# Main.net
KiCad netlist of a schematic drawn in Altium Designer
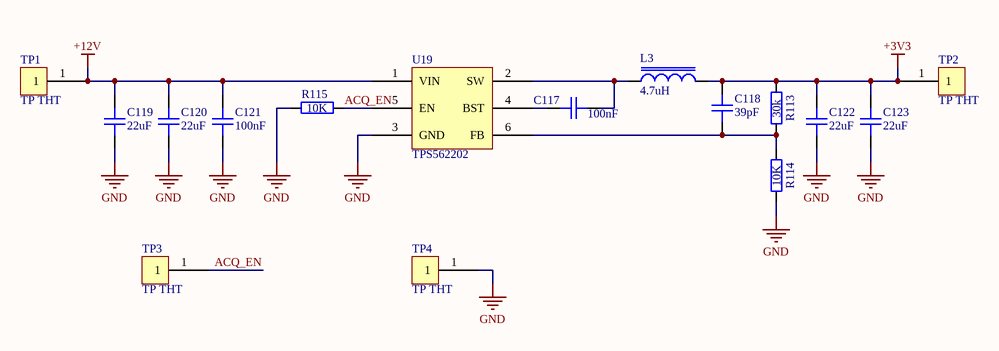
[diagram p0: Main.SchDoc]

(export (version "E")
  (design (tool "Eeschema 10.0.6"))
  (components
    (comp (ref "C117")
      (value "100nF")
      (footprint "GEN_C_0402")
      (fields
        (field (name "HOUSE PART NUMBER") "C-100nF-0402-002")
        (field (name "MANUFACTURER") "Murata")
        (field (name "MANUFACTURER PART NUMBER") "GCM155R71C104KA55D")
      )
      (libsource (lib "DSO") (part "CAP 100nF 16V X7R 0402"))
    )
    (comp (ref "C118")
      (value "39pF")
      (footprint "GEN_C_0402")
      (fields
        (field (name "MANUFACTURER") "KEMET")
        (field (name "HOUSE PART NUMBER") "C-39pF-0402-002")
        (field (name "MANUFACTURER PART NUMBER") "C0402C390J5GACTU")
      )
      (libsource (lib "DSO") (part "CAP 39pF 50V C0G 0402"))
    )
    (comp (ref "C119")
      (value "22uF")
      (footprint "GEN_C_0805")
      (fields
        (field (name "HOUSE PART NUMBER") "C-22uF-0805-002")
        (field (name "MANUFACTURER") "Murata")
        (field (name "MANUFACTURER PART NUMBER") "GRM21BR61E226ME44L")
      )
      (libsource (lib "DSO") (part "CAP 22uF 25V X5R 0805"))
    )
    (comp (ref "C120")
      (value "22uF")
      (footprint "GEN_C_0805")
      (fields
        (field (name "HOUSE PART NUMBER") "C-22uF-0805-002")
        (field (name "MANUFACTURER") "Murata")
        (field (name "MANUFACTURER PART NUMBER") "GRM21BR61E226ME44L")
      )
      (libsource (lib "DSO") (part "CAP 22uF 25V X5R 0805"))
    )
    (comp (ref "C121")
      (value "100nF")
      (footprint "GEN_C_0402")
      (fields
        (field (name "HOUSE PART NUMBER") "C-100nF-0402-002")
        (field (name "MANUFACTURER") "Murata")
        (field (name "MANUFACTURER PART NUMBER") "GCM155R71C104KA55D")
      )
      (libsource (lib "DSO") (part "CAP 100nF 16V X7R 0402"))
    )
    (comp (ref "C122")
      (value "22uF")
      (footprint "GEN_C_0805")
      (fields
        (field (name "HOUSE PART NUMBER") "C-22uF-0805-002")
        (field (name "MANUFACTURER") "Murata")
        (field (name "MANUFACTURER PART NUMBER") "GRM21BR61E226ME44L")
      )
      (libsource (lib "DSO") (part "CAP 22uF 25V X5R 0805"))
    )
    (comp (ref "C123")
      (value "22uF")
      (footprint "GEN_C_0805")
      (fields
        (field (name "HOUSE PART NUMBER") "C-22uF-0805-002")
        (field (name "MANUFACTURER") "Murata")
        (field (name "MANUFACTURER PART NUMBER") "GRM21BR61E226ME44L")
      )
      (libsource (lib "DSO") (part "CAP 22uF 25V X5R 0805"))
    )
    (comp (ref "L3")
      (value "4.7uH")
      (footprint "TY_IND_NRS5030")
      (fields
        (field (name "MANUFACTURER") "Taiyo Yuden")
        (field (name "MANUFACTURER PART NUMBER") "NRS5030T4R7MMGJ")
      )
      (libsource (lib "DSO") (part "IND 4.7uH 2.6A 35 MOHM SMD"))
    )
    (comp (ref "R113")
      (value "30k")
      (footprint "GEN_R_0402")
      (fields
        (field (name "TOLERANCE") "1%")
        (field (name "MANUFACTURER") "Yageo")
        (field (name "MANUFACTURER PART NUMBER") "RC0402FR-0730KL")
      )
      (libsource (lib "DSO") (part "RES 30K OHM 1% 1/16W 0402"))
    )
    (comp (ref "R114")
      (value "10K")
      (footprint "GEN_R_0402")
      (fields
        (field (name "TOLERANCE") "1%")
        (field (name "MANUFACTURER") "Panasonic")
        (field (name "MANUFACTURER PART NUMBER") "ERJ-2RKF1002X")
      )
      (libsource (lib "DSO") (part "RES 10K OHM 1% 1/10W 0402"))
    )
    (comp (ref "R115")
      (value "10K")
      (footprint "GEN_R_0402")
      (fields
        (field (name "TOLERANCE") "1%")
        (field (name "MANUFACTURER") "Panasonic")
        (field (name "MANUFACTURER PART NUMBER") "ERJ-2RKF1002X")
      )
      (libsource (lib "") (part "RES 10K OHM 1% 1/10W 0402_1"))
    )
    (comp (ref "TP1") (value "TP THT") (footprint "GEN_1_Pin_TH_TP") (libsource (lib "DSO") (part "TP THT")))
    (comp (ref "TP2") (value "TP THT") (footprint "GEN_1_Pin_TH_TP") (libsource (lib "") (part "TP THT_1")))
    (comp (ref "TP3") (value "TP THT") (footprint "GEN_1_Pin_TH_TP") (libsource (lib "DSO") (part "TP THT")))
    (comp (ref "TP4") (value "TP THT") (footprint "GEN_1_Pin_TH_TP") (libsource (lib "DSO") (part "TP THT")))
    (comp (ref "U19")
      (value "TPS562202")
      (footprint "TI_SOT563_DRL0006A")
      (libsource (lib "DSO") (part "IC BUCK TPS562202"))
    )
  )
  (nets
    (net (code "1") (name "+3V3") (class "Default")
      (node (ref "C118") (pin "2") (pinfunction "2_2") (pintype "passive"))
      (node (ref "C122") (pin "2") (pinfunction "2_2") (pintype "passive"))
      (node (ref "C123") (pin "2") (pinfunction "2_2") (pintype "passive"))
      (node (ref "L3") (pin "2") (pinfunction "2_2") (pintype "passive"))
      (node (ref "R113") (pin "2") (pinfunction "2_2") (pintype "passive"))
      (node (ref "TP2") (pin "1") (pinfunction "1_1") (pintype "passive"))
    )
    (net (code "2") (name "+12V") (class "Default")
      (node (ref "C119") (pin "2") (pinfunction "2_2") (pintype "passive"))
      (node (ref "C120") (pin "2") (pinfunction "2_2") (pintype "passive"))
      (node (ref "C121") (pin "1") (pinfunction "1_1") (pintype "passive"))
      (node (ref "TP1") (pin "1") (pinfunction "1_1") (pintype "passive"))
      (node (ref "U19") (pin "1") (pinfunction "VIN_1") (pintype "power_in"))
    )
    (net (code "3") (name "/ACQ_EN") (class "Default")
      (node (ref "R115") (pin "1") (pinfunction "1_1") (pintype "passive"))
      (node (ref "TP3") (pin "1") (pinfunction "1_1") (pintype "passive"))
      (node (ref "U19") (pin "5") (pinfunction "EN_5") (pintype "passive"))
    )
    (net (code "4") (name "GND") (class "Default")
      (node (ref "C119") (pin "1") (pinfunction "1_1") (pintype "passive"))
      (node (ref "C120") (pin "1") (pinfunction "1_1") (pintype "passive"))
      (node (ref "C121") (pin "2") (pinfunction "2_2") (pintype "passive"))
      (node (ref "C122") (pin "1") (pinfunction "1_1") (pintype "passive"))
      (node (ref "C123") (pin "1") (pinfunction "1_1") (pintype "passive"))
      (node (ref "R114") (pin "1") (pinfunction "1_1") (pintype "passive"))
      (node (ref "R115") (pin "2") (pinfunction "2_2") (pintype "passive"))
      (node (ref "TP4") (pin "1") (pinfunction "1_1") (pintype "passive"))
      (node (ref "U19") (pin "3") (pinfunction "GND_3") (pintype "power_in"))
    )
    (net (code "5") (name "Net-(U19-BST)") (class "Default")
      (node (ref "C117") (pin "2") (pinfunction "2_2") (pintype "passive"))
      (node (ref "U19") (pin "4") (pinfunction "BST_4") (pintype "passive"))
    )
    (net (code "6") (name "Net-(U19-FB)") (class "Default")
      (node (ref "C118") (pin "1") (pinfunction "1_1") (pintype "passive"))
      (node (ref "R113") (pin "1") (pinfunction "1_1") (pintype "passive"))
      (node (ref "R114") (pin "2") (pinfunction "2_2") (pintype "passive"))
      (node (ref "U19") (pin "6") (pinfunction "FB_6") (pintype "passive"))
    )
    (net (code "7") (name "Net-(U19-SW)") (class "Default")
      (node (ref "C117") (pin "1") (pinfunction "1_1") (pintype "passive"))
      (node (ref "L3") (pin "1") (pinfunction "1_1") (pintype "passive"))
      (node (ref "U19") (pin "2") (pinfunction "SW_2") (pintype "passive"))
    )
  )
)
